# FSR_Array_Sch.net
KiCad netlist of a schematic drawn in Altium Designer
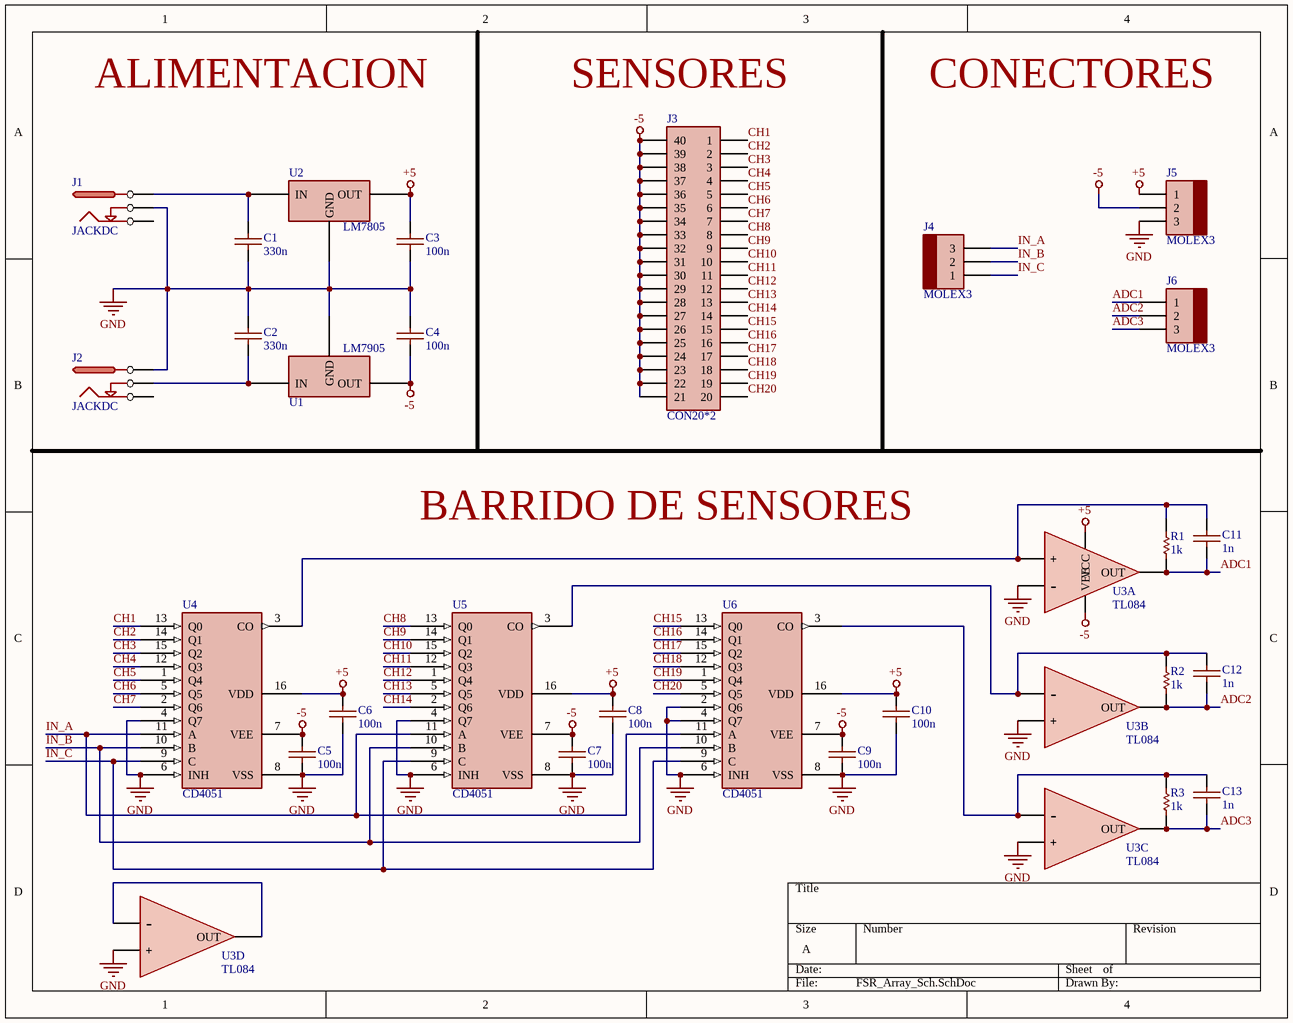
[diagram p0: FSR_Array_Sch.SchDoc]

(export (version "E")
  (design (tool "Eeschema 10.0.6"))
  (components
    (comp (ref "C1") (value "330n") (footprint "0805") (libsource (lib "SchLib_Recinto") (part "CAP")))
    (comp (ref "C2") (value "330n") (footprint "0805") (libsource (lib "SchLib_Recinto") (part "CAP")))
    (comp (ref "C3") (value "100n") (footprint "0805") (libsource (lib "SchLib_Recinto") (part "CAP")))
    (comp (ref "C4") (value "100n") (footprint "0805") (libsource (lib "SchLib_Recinto") (part "CAP")))
    (comp (ref "C5") (value "100n") (footprint "0805") (libsource (lib "SchLib_Recinto") (part "CAP")))
    (comp (ref "C6") (value "100n") (footprint "0805") (libsource (lib "SchLib_Recinto") (part "CAP")))
    (comp (ref "C7") (value "100n") (footprint "0805") (libsource (lib "SchLib_Recinto") (part "CAP")))
    (comp (ref "C8") (value "100n") (footprint "0805") (libsource (lib "SchLib_Recinto") (part "CAP")))
    (comp (ref "C9") (value "100n") (footprint "0805") (libsource (lib "SchLib_Recinto") (part "CAP")))
    (comp (ref "C10") (value "100n") (footprint "0805") (libsource (lib "SchLib_Recinto") (part "CAP")))
    (comp (ref "C11") (value "1n") (footprint "0805") (libsource (lib "SchLib_Recinto") (part "CAP")))
    (comp (ref "C12") (value "1n") (footprint "0805") (libsource (lib "SchLib_Recinto") (part "CAP")))
    (comp (ref "C13") (value "1n") (footprint "0805") (libsource (lib "SchLib_Recinto") (part "CAP")))
    (comp (ref "J1") (value "JACKDC") (footprint "JACKDC") (libsource (lib "SchLib_Recinto") (part "JACKDC")))
    (comp (ref "J2") (value "JACKDC") (footprint "JACKDC") (libsource (lib "SchLib_Recinto") (part "JACKDC")))
    (comp (ref "J3")
      (value "CON20*2")
      (footprint "SIP20*2")
      (libsource (lib "SchLib_Recinto") (part "CON20*2"))
    )
    (comp (ref "J4") (value "MOLEX3") (footprint "MOLEX3") (libsource (lib "SchLib_Recinto") (part "MOLEX3")))
    (comp (ref "J5") (value "MOLEX3") (footprint "MOLEX3") (libsource (lib "") (part "MOLEX3_1")))
    (comp (ref "J6") (value "MOLEX3") (footprint "MOLEX3") (libsource (lib "") (part "MOLEX3_1")))
    (comp (ref "R1") (value "1k") (footprint "0805") (libsource (lib "SchLib_Recinto") (part "RES")))
    (comp (ref "R2") (value "1k") (footprint "0805") (libsource (lib "SchLib_Recinto") (part "RES")))
    (comp (ref "R3") (value "1k") (footprint "0805") (libsource (lib "SchLib_Recinto") (part "RES")))
    (comp (ref "U1")
      (value "LM7905")
      (footprint "TO-220 V")
      (libsource (lib "SchLib_Recinto") (part "LM7905"))
    )
    (comp (ref "U2")
      (value "LM7805")
      (footprint "TO-220 V")
      (libsource (lib "SchLib_Recinto") (part "LM7805"))
    )
    (comp (ref "U3") (value "TL084") (footprint "SOIC-14") (libsource (lib "SchLib_Recinto") (part "TL084")))
    (comp (ref "U4") (value "CD4051") (footprint "CD4051") (libsource (lib "SchLib_Recinto") (part "CD4051")))
    (comp (ref "U5") (value "CD4051") (footprint "CD4051") (libsource (lib "SchLib_Recinto") (part "CD4051")))
    (comp (ref "U6") (value "CD4051") (footprint "CD4051") (libsource (lib "SchLib_Recinto") (part "CD4051")))
  )
  (nets
    (net (code "1") (name "+5") (class "Default")
      (node (ref "C10") (pin "1") (pintype "passive"))
      (node (ref "C3") (pin "1") (pintype "passive"))
      (node (ref "C6") (pin "1") (pintype "passive"))
      (node (ref "C8") (pin "1") (pintype "passive"))
      (node (ref "J5") (pin "1") (pinfunction "1_1") (pintype "passive"))
      (node (ref "U2") (pin "2") (pinfunction "OUT_2") (pintype "passive"))
      (node (ref "U3") (pin "4") (pinfunction "VCC_4") (pintype "passive"))
      (node (ref "U4") (pin "16") (pinfunction "VDD_16") (pintype "power_in"))
      (node (ref "U5") (pin "16") (pinfunction "VDD_16") (pintype "power_in"))
      (node (ref "U6") (pin "16") (pinfunction "VDD_16") (pintype "power_in"))
    )
    (net (code "2") (name "-5") (class "Default")
      (node (ref "C4") (pin "2") (pintype "passive"))
      (node (ref "C5") (pin "1") (pintype "passive"))
      (node (ref "C7") (pin "1") (pintype "passive"))
      (node (ref "C9") (pin "1") (pintype "passive"))
      (node (ref "J3") (pin "21") (pinfunction "21_21") (pintype "passive"))
      (node (ref "J3") (pin "22") (pinfunction "22_22") (pintype "passive"))
      (node (ref "J3") (pin "23") (pinfunction "23_23") (pintype "passive"))
      (node (ref "J3") (pin "24") (pinfunction "24_24") (pintype "passive"))
      (node (ref "J3") (pin "25") (pinfunction "25_25") (pintype "passive"))
      (node (ref "J3") (pin "26") (pinfunction "26_26") (pintype "passive"))
      (node (ref "J3") (pin "27") (pinfunction "27_27") (pintype "passive"))
      (node (ref "J3") (pin "28") (pinfunction "28_28") (pintype "passive"))
      (node (ref "J3") (pin "29") (pinfunction "29_29") (pintype "passive"))
      (node (ref "J3") (pin "30") (pinfunction "30_30") (pintype "passive"))
      (node (ref "J3") (pin "31") (pinfunction "31_31") (pintype "passive"))
      (node (ref "J3") (pin "32") (pinfunction "32_32") (pintype "passive"))
      (node (ref "J3") (pin "33") (pinfunction "33_33") (pintype "passive"))
      (node (ref "J3") (pin "34") (pinfunction "34_34") (pintype "passive"))
      (node (ref "J3") (pin "35") (pinfunction "35_35") (pintype "passive"))
      (node (ref "J3") (pin "36") (pinfunction "36_36") (pintype "passive"))
      (node (ref "J3") (pin "37") (pinfunction "37_37") (pintype "passive"))
      (node (ref "J3") (pin "38") (pinfunction "38_38") (pintype "passive"))
      (node (ref "J3") (pin "39") (pinfunction "39_39") (pintype "passive"))
      (node (ref "J3") (pin "40") (pinfunction "40_40") (pintype "passive"))
      (node (ref "J5") (pin "2") (pinfunction "2_2") (pintype "passive"))
      (node (ref "U1") (pin "3") (pinfunction "OUT_3") (pintype "passive"))
      (node (ref "U3") (pin "11") (pinfunction "VEE_11") (pintype "passive"))
      (node (ref "U4") (pin "7") (pinfunction "VEE_7") (pintype "power_in"))
      (node (ref "U5") (pin "7") (pinfunction "VEE_7") (pintype "power_in"))
      (node (ref "U6") (pin "7") (pinfunction "VEE_7") (pintype "power_in"))
    )
    (net (code "3") (name "/ADC1") (class "Default")
      (node (ref "C11") (pin "2") (pintype "passive"))
      (node (ref "J6") (pin "1") (pinfunction "1_1") (pintype "passive"))
      (node (ref "R1") (pin "1") (pinfunction "1_1") (pintype "passive"))
      (node (ref "U3") (pin "1") (pinfunction "OUT_1") (pintype "passive"))
    )
    (net (code "4") (name "/ADC2") (class "Default")
      (node (ref "C12") (pin "2") (pintype "passive"))
      (node (ref "J6") (pin "2") (pinfunction "2_2") (pintype "passive"))
      (node (ref "R2") (pin "1") (pinfunction "1_1") (pintype "passive"))
      (node (ref "U3") (pin "7") (pinfunction "OUT_7") (pintype "passive"))
    )
    (net (code "5") (name "/ADC3") (class "Default")
      (node (ref "C13") (pin "2") (pintype "passive"))
      (node (ref "J6") (pin "3") (pinfunction "3_3") (pintype "passive"))
      (node (ref "R3") (pin "1") (pinfunction "1_1") (pintype "passive"))
      (node (ref "U3") (pin "8") (pinfunction "OUT_8") (pintype "passive"))
    )
    (net (code "6") (name "/CH1") (class "Default")
      (node (ref "J3") (pin "1") (pinfunction "1_1") (pintype "passive"))
      (node (ref "U4") (pin "13") (pinfunction "Q0_13") (pintype "input"))
    )
    (net (code "7") (name "/CH2") (class "Default")
      (node (ref "J3") (pin "2") (pinfunction "2_2") (pintype "passive"))
      (node (ref "U4") (pin "14") (pinfunction "Q1_14") (pintype "input"))
    )
    (net (code "8") (name "/CH3") (class "Default")
      (node (ref "J3") (pin "3") (pinfunction "3_3") (pintype "passive"))
      (node (ref "U4") (pin "15") (pinfunction "Q2_15") (pintype "input"))
    )
    (net (code "9") (name "/CH4") (class "Default")
      (node (ref "J3") (pin "4") (pinfunction "4_4") (pintype "passive"))
      (node (ref "U4") (pin "12") (pinfunction "Q3_12") (pintype "input"))
    )
    (net (code "10") (name "/CH5") (class "Default")
      (node (ref "J3") (pin "5") (pinfunction "5_5") (pintype "passive"))
      (node (ref "U4") (pin "1") (pinfunction "Q4_1") (pintype "input"))
    )
    (net (code "11") (name "/CH6") (class "Default")
      (node (ref "J3") (pin "6") (pinfunction "6_6") (pintype "passive"))
      (node (ref "U4") (pin "5") (pinfunction "Q5_5") (pintype "input"))
    )
    (net (code "12") (name "/CH7") (class "Default")
      (node (ref "J3") (pin "7") (pinfunction "7_7") (pintype "passive"))
      (node (ref "U4") (pin "2") (pinfunction "Q6_2") (pintype "input"))
    )
    (net (code "13") (name "/CH8") (class "Default")
      (node (ref "J3") (pin "8") (pinfunction "8_8") (pintype "passive"))
      (node (ref "U5") (pin "13") (pinfunction "Q0_13") (pintype "input"))
    )
    (net (code "14") (name "/CH9") (class "Default")
      (node (ref "J3") (pin "9") (pinfunction "9_9") (pintype "passive"))
      (node (ref "U5") (pin "14") (pinfunction "Q1_14") (pintype "input"))
    )
    (net (code "15") (name "/CH10") (class "Default")
      (node (ref "J3") (pin "10") (pinfunction "10_10") (pintype "passive"))
      (node (ref "U5") (pin "15") (pinfunction "Q2_15") (pintype "input"))
    )
    (net (code "16") (name "/CH11") (class "Default")
      (node (ref "J3") (pin "11") (pinfunction "11_11") (pintype "passive"))
      (node (ref "U5") (pin "12") (pinfunction "Q3_12") (pintype "input"))
    )
    (net (code "17") (name "/CH12") (class "Default")
      (node (ref "J3") (pin "12") (pinfunction "12_12") (pintype "passive"))
      (node (ref "U5") (pin "1") (pinfunction "Q4_1") (pintype "input"))
    )
    (net (code "18") (name "/CH13") (class "Default")
      (node (ref "J3") (pin "13") (pinfunction "13_13") (pintype "passive"))
      (node (ref "U5") (pin "5") (pinfunction "Q5_5") (pintype "input"))
    )
    (net (code "19") (name "/CH14") (class "Default")
      (node (ref "J3") (pin "14") (pinfunction "14_14") (pintype "passive"))
      (node (ref "U5") (pin "2") (pinfunction "Q6_2") (pintype "input"))
    )
    (net (code "20") (name "/CH15") (class "Default")
      (node (ref "J3") (pin "15") (pinfunction "15_15") (pintype "passive"))
      (node (ref "U6") (pin "13") (pinfunction "Q0_13") (pintype "input"))
    )
    (net (code "21") (name "/CH16") (class "Default")
      (node (ref "J3") (pin "16") (pinfunction "16_16") (pintype "passive"))
      (node (ref "U6") (pin "14") (pinfunction "Q1_14") (pintype "input"))
    )
    (net (code "22") (name "/CH17") (class "Default")
      (node (ref "J3") (pin "17") (pinfunction "17_17") (pintype "passive"))
      (node (ref "U6") (pin "15") (pinfunction "Q2_15") (pintype "input"))
    )
    (net (code "23") (name "/CH18") (class "Default")
      (node (ref "J3") (pin "18") (pinfunction "18_18") (pintype "passive"))
      (node (ref "U6") (pin "12") (pinfunction "Q3_12") (pintype "input"))
    )
    (net (code "24") (name "/CH19") (class "Default")
      (node (ref "J3") (pin "19") (pinfunction "19_19") (pintype "passive"))
      (node (ref "U6") (pin "1") (pinfunction "Q4_1") (pintype "input"))
    )
    (net (code "25") (name "/CH20") (class "Default")
      (node (ref "J3") (pin "20") (pinfunction "20_20") (pintype "passive"))
      (node (ref "U6") (pin "5") (pinfunction "Q5_5") (pintype "input"))
    )
    (net (code "26") (name "/IN_A") (class "Default")
      (node (ref "J4") (pin "3") (pinfunction "3_3") (pintype "passive"))
      (node (ref "U4") (pin "11") (pinfunction "A_11") (pintype "input"))
      (node (ref "U5") (pin "11") (pinfunction "A_11") (pintype "input"))
      (node (ref "U6") (pin "11") (pinfunction "A_11") (pintype "input"))
    )
    (net (code "27") (name "/IN_B") (class "Default")
      (node (ref "J4") (pin "2") (pinfunction "2_2") (pintype "passive"))
      (node (ref "U4") (pin "10") (pinfunction "B_10") (pintype "input"))
      (node (ref "U5") (pin "10") (pinfunction "B_10") (pintype "input"))
      (node (ref "U6") (pin "10") (pinfunction "B_10") (pintype "input"))
    )
    (net (code "28") (name "/IN_C") (class "Default")
      (node (ref "J4") (pin "1") (pinfunction "1_1") (pintype "passive"))
      (node (ref "U4") (pin "9") (pinfunction "C_9") (pintype "input"))
      (node (ref "U5") (pin "9") (pinfunction "C_9") (pintype "input"))
      (node (ref "U6") (pin "9") (pinfunction "C_9") (pintype "input"))
    )
    (net (code "29") (name "GND") (class "Default")
      (node (ref "C1") (pin "2") (pintype "passive"))
      (node (ref "C10") (pin "2") (pintype "passive"))
      (node (ref "C2") (pin "1") (pintype "passive"))
      (node (ref "C3") (pin "2") (pintype "passive"))
      (node (ref "C4") (pin "1") (pintype "passive"))
      (node (ref "C5") (pin "2") (pintype "passive"))
      (node (ref "C6") (pin "2") (pintype "passive"))
      (node (ref "C7") (pin "2") (pintype "passive"))
      (node (ref "C8") (pin "2") (pintype "passive"))
      (node (ref "C9") (pin "2") (pintype "passive"))
      (node (ref "J1") (pin "2") (pinfunction "2_2") (pintype "passive"))
      (node (ref "J2") (pin "1") (pinfunction "1_1") (pintype "passive"))
      (node (ref "J5") (pin "3") (pinfunction "3_3") (pintype "passive"))
      (node (ref "U1") (pin "1") (pinfunction "GND_1") (pintype "passive"))
      (node (ref "U2") (pin "1") (pinfunction "GND_1") (pintype "passive"))
      (node (ref "U3") (pin "10") (pinfunction "+_10") (pintype "passive"))
      (node (ref "U3") (pin "12") (pinfunction "+_12") (pintype "passive"))
      (node (ref "U3") (pin "2") (pinfunction "-_2") (pintype "passive"))
      (node (ref "U3") (pin "5") (pinfunction "+_5") (pintype "passive"))
      (node (ref "U4") (pin "4") (pinfunction "Q7_4") (pintype "input"))
      (node (ref "U4") (pin "6") (pinfunction "INH_6") (pintype "input"))
      (node (ref "U4") (pin "8") (pinfunction "VSS_8") (pintype "power_in"))
      (node (ref "U5") (pin "4") (pinfunction "Q7_4") (pintype "input"))
      (node (ref "U5") (pin "6") (pinfunction "INH_6") (pintype "input"))
      (node (ref "U5") (pin "8") (pinfunction "VSS_8") (pintype "power_in"))
      (node (ref "U6") (pin "2") (pinfunction "Q6_2") (pintype "input"))
      (node (ref "U6") (pin "4") (pinfunction "Q7_4") (pintype "input"))
      (node (ref "U6") (pin "6") (pinfunction "INH_6") (pintype "input"))
      (node (ref "U6") (pin "8") (pinfunction "VSS_8") (pintype "power_in"))
    )
    (net (code "30") (name "Net-(U1-IN)") (class "Default")
      (node (ref "C2") (pin "2") (pintype "passive"))
      (node (ref "J2") (pin "2") (pinfunction "2_2") (pintype "passive"))
      (node (ref "U1") (pin "2") (pinfunction "IN_2") (pintype "passive"))
    )
    (net (code "31") (name "Net-(U2-IN)") (class "Default")
      (node (ref "C1") (pin "1") (pintype "passive"))
      (node (ref "J1") (pin "1") (pinfunction "1_1") (pintype "passive"))
      (node (ref "U2") (pin "3") (pinfunction "IN_3") (pintype "passive"))
    )
    (net (code "32") (name "Net-(U3A-+)") (class "Default")
      (node (ref "C11") (pin "1") (pintype "passive"))
      (node (ref "R1") (pin "2") (pinfunction "2_2") (pintype "passive"))
      (node (ref "U3") (pin "3") (pinfunction "+_3") (pintype "passive"))
      (node (ref "U4") (pin "3") (pinfunction "CO_3") (pintype "output"))
    )
    (net (code "33") (name "Net-(U3B--)") (class "Default")
      (node (ref "C12") (pin "1") (pintype "passive"))
      (node (ref "R2") (pin "2") (pinfunction "2_2") (pintype "passive"))
      (node (ref "U3") (pin "6") (pinfunction "-_6") (pintype "passive"))
      (node (ref "U5") (pin "3") (pinfunction "CO_3") (pintype "output"))
    )
    (net (code "34") (name "Net-(U3C--)") (class "Default")
      (node (ref "C13") (pin "1") (pintype "passive"))
      (node (ref "R3") (pin "2") (pinfunction "2_2") (pintype "passive"))
      (node (ref "U3") (pin "9") (pinfunction "-_9") (pintype "passive"))
      (node (ref "U6") (pin "3") (pinfunction "CO_3") (pintype "output"))
    )
    (net (code "35") (name "Net-(U3D--)") (class "Default")
      (node (ref "U3") (pin "13") (pinfunction "-_13") (pintype "passive"))
      (node (ref "U3") (pin "14") (pinfunction "OUT_14") (pintype "passive"))
    )
    (net (code "36") (name "unconnected-(J1-Pad3)") (class "Default")
      (node (ref "J1") (pin "3") (pinfunction "3_3") (pintype "passive"))
    )
    (net (code "37") (name "unconnected-(J2-Pad3)") (class "Default")
      (node (ref "J2") (pin "3") (pinfunction "3_3") (pintype "passive"))
    )
  )
)
